# 02_-_Connectors.net
KiCad netlist of a schematic drawn in Altium Designer
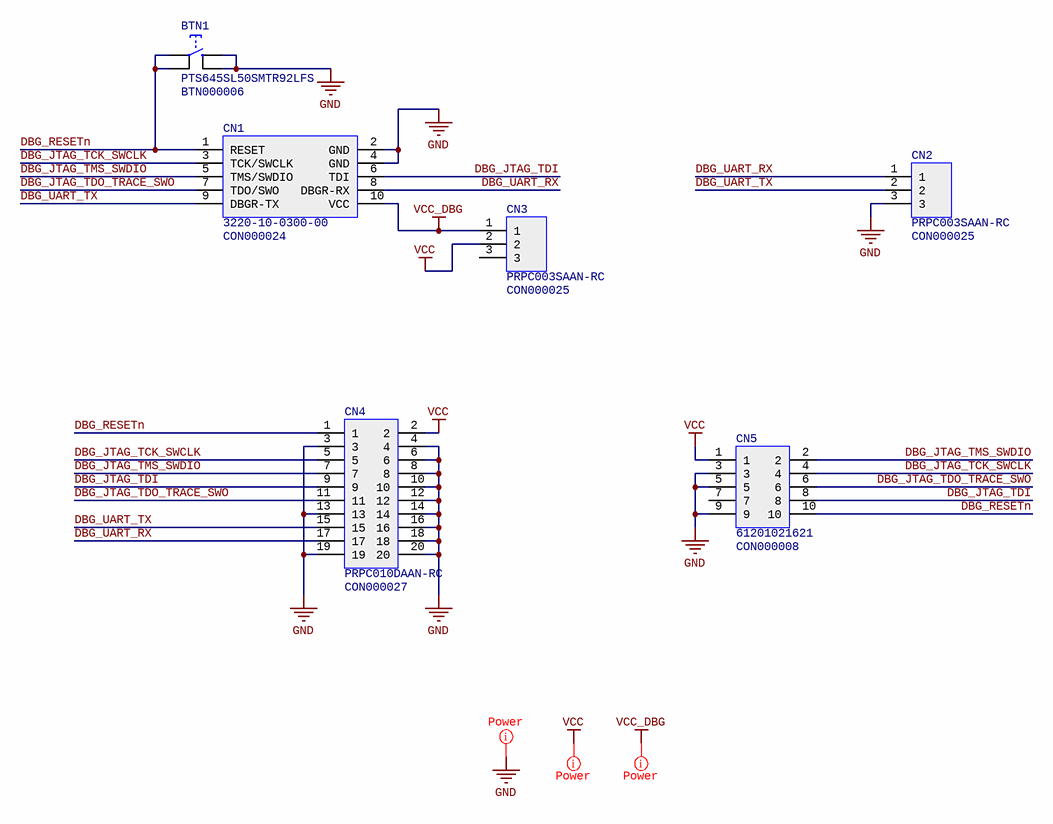
[diagram p0: [02] - Connectors.SchDoc]

(export (version "E")
  (design (tool "Eeschema 10.0.6"))
  (components
    (comp (ref "BTN1")
      (value "PTS645SL50SMTR92LFS")
      (footprint "BTN-SMD-PTS645-CK")
      (description "BTN TACT SPST-NO 12V 50mA SMD BLACK")
      (fields (field (name "MANUFACTURER") "ITT C&K") (field (name "INTERNAL PART NUMBER") "BTN000006"))
      (libsource (lib "Altium_Lib_Standard") (part "PTS645SL50SMTR92LFS"))
    )
    (comp (ref "CN1")
      (value "3220-10-0300-00")
      (footprint "CON-SMD-PINHEADER-SHIELDED-1.27MM-10POS-2X5-3220-10-0300-00-CNC-TECH")
      (description "CON PINHDR SMD 1.27MM SHIELDED KEYED CNC TECH 10POS")
      (fields (field (name "INTERNAL PART NUMBER") "CON000024"))
      (libsource (lib "Altium_Lib_Standard") (part "3220-10-0300-00"))
    )
    (comp (ref "CN2")
      (value "PRPC003SAAN-RC")
      (footprint "CON-THT-PINHEADER-2.54MM-3POS-1X3")
      (description "CON PINHDR 2.54MM 1x03")
      (fields (field (name "MANUFACTURER") "Sullins") (field (name "INTERNAL PART NUMBER") "CON000025"))
      (libsource (lib "Altium_Lib_Standard") (part "PRPC003SAAN-RC"))
    )
    (comp (ref "CN3")
      (value "PRPC003SAAN-RC")
      (footprint "CON-THT-PINHEADER-2.54MM-3POS-1X3")
      (description "CON PINHDR 2.54MM 1x03")
      (fields (field (name "MANUFACTURER") "Sullins") (field (name "INTERNAL PART NUMBER") "CON000025"))
      (libsource (lib "Altium_Lib_Standard") (part "PRPC003SAAN-RC"))
    )
    (comp (ref "CN4")
      (value "PRPC010DAAN-RC")
      (footprint "CON-THT-PINHEADER-2.54MM-20POS-2X10")
      (description "CON PINHDR 2.54MM 2x10")
      (fields (field (name "MANUFACTURER") "Sullins") (field (name "INTERNAL PART NUMBER") "CON000027"))
      (libsource (lib "Altium_Lib_Standard") (part "PRPC010DAAN-RC"))
    )
    (comp (ref "CN5")
      (value "61201021621")
      (footprint "CON-THT-PINHEADER-SHIELDED-2.54MM-10POS-61201021621-WURTH")
      (description "CON PINHDR 2.54MM SHIELDED 2x05 WURTH")
      (fields
        (field (name "MANUFACTURER") "Wurth Electronics")
        (field (name "INTERNAL PART NUMBER") "CON000008")
      )
      (libsource (lib "Altium_Lib_Standard") (part "61201021621"))
    )
  )
  (nets
    (net (code "1") (name "/DBG_JTAG_TCK_SWCLK") (class "Default")
      (node (ref "CN1") (pin "3") (pinfunction "TCK/SWCLK_3") (pintype "passive"))
      (node (ref "CN4") (pin "5") (pinfunction "5_5") (pintype "passive"))
      (node (ref "CN5") (pin "4") (pinfunction "4_4") (pintype "passive"))
    )
    (net (code "2") (name "/DBG_JTAG_TDI") (class "Default")
      (node (ref "CN1") (pin "6") (pinfunction "TDI_6") (pintype "passive"))
      (node (ref "CN4") (pin "9") (pinfunction "9_9") (pintype "passive"))
      (node (ref "CN5") (pin "8") (pinfunction "8_8") (pintype "passive"))
    )
    (net (code "3") (name "/DBG_JTAG_TDO_TRACE_SWO") (class "Default")
      (node (ref "CN1") (pin "7") (pinfunction "TDO/SWO_7") (pintype "passive"))
      (node (ref "CN4") (pin "11") (pinfunction "11_11") (pintype "passive"))
      (node (ref "CN5") (pin "6") (pinfunction "6_6") (pintype "passive"))
    )
    (net (code "4") (name "/DBG_JTAG_TMS_SWDIO") (class "Default")
      (node (ref "CN1") (pin "5") (pinfunction "TMS/SWDIO_5") (pintype "passive"))
      (node (ref "CN4") (pin "7") (pinfunction "7_7") (pintype "passive"))
      (node (ref "CN5") (pin "2") (pinfunction "2_2") (pintype "passive"))
    )
    (net (code "5") (name "/DBG_RESETn") (class "Default")
      (node (ref "BTN1") (pin "1") (pinfunction "1_1") (pintype "passive"))
      (node (ref "BTN1") (pin "2") (pinfunction "2_2") (pintype "passive"))
      (node (ref "CN1") (pin "1") (pinfunction "RESET_1") (pintype "passive"))
      (node (ref "CN4") (pin "1") (pinfunction "1_1") (pintype "passive"))
      (node (ref "CN5") (pin "10") (pinfunction "10_10") (pintype "passive"))
    )
    (net (code "6") (name "/DBG_UART_RX") (class "Default")
      (node (ref "CN1") (pin "8") (pinfunction "DBGR-RX_8") (pintype "passive"))
      (node (ref "CN2") (pin "1") (pinfunction "1_1") (pintype "passive"))
      (node (ref "CN4") (pin "17") (pinfunction "17_17") (pintype "passive"))
    )
    (net (code "7") (name "/DBG_UART_TX") (class "Default")
      (node (ref "CN1") (pin "9") (pinfunction "DBGR-TX_9") (pintype "passive"))
      (node (ref "CN2") (pin "2") (pinfunction "2_2") (pintype "passive"))
      (node (ref "CN4") (pin "15") (pinfunction "15_15") (pintype "passive"))
    )
    (net (code "8") (name "GND") (class "Default")
      (node (ref "BTN1") (pin "3") (pinfunction "3_3") (pintype "passive"))
      (node (ref "BTN1") (pin "4") (pinfunction "4_4") (pintype "passive"))
      (node (ref "CN1") (pin "2") (pinfunction "GND_2") (pintype "passive"))
      (node (ref "CN1") (pin "4") (pinfunction "GND_4") (pintype "passive"))
      (node (ref "CN2") (pin "3") (pinfunction "3_3") (pintype "passive"))
      (node (ref "CN4") (pin "10") (pinfunction "10_10") (pintype "passive"))
      (node (ref "CN4") (pin "12") (pinfunction "12_12") (pintype "passive"))
      (node (ref "CN4") (pin "13") (pinfunction "13_13") (pintype "passive"))
      (node (ref "CN4") (pin "14") (pinfunction "14_14") (pintype "passive"))
      (node (ref "CN4") (pin "16") (pinfunction "16_16") (pintype "passive"))
      (node (ref "CN4") (pin "18") (pinfunction "18_18") (pintype "passive"))
      (node (ref "CN4") (pin "19") (pinfunction "19_19") (pintype "passive"))
      (node (ref "CN4") (pin "20") (pinfunction "20_20") (pintype "passive"))
      (node (ref "CN4") (pin "3") (pinfunction "3_3") (pintype "passive"))
      (node (ref "CN4") (pin "4") (pinfunction "4_4") (pintype "passive"))
      (node (ref "CN4") (pin "6") (pinfunction "6_6") (pintype "passive"))
      (node (ref "CN4") (pin "8") (pinfunction "8_8") (pintype "passive"))
      (node (ref "CN5") (pin "3") (pinfunction "3_3") (pintype "passive"))
      (node (ref "CN5") (pin "5") (pinfunction "5_5") (pintype "passive"))
      (node (ref "CN5") (pin "9") (pinfunction "9_9") (pintype "passive"))
    )
    (net (code "9") (name "VCC") (class "Default")
      (node (ref "CN3") (pin "2") (pinfunction "2_2") (pintype "passive"))
      (node (ref "CN4") (pin "2") (pinfunction "2_2") (pintype "passive"))
      (node (ref "CN5") (pin "1") (pinfunction "1_1") (pintype "passive"))
    )
    (net (code "10") (name "VCC_DBG") (class "Default")
      (node (ref "CN1") (pin "10") (pinfunction "VCC_10") (pintype "passive"))
      (node (ref "CN3") (pin "1") (pinfunction "1_1") (pintype "passive"))
    )
    (net (code "11") (name "unconnected-(CN3-Pad3)") (class "Default")
      (node (ref "CN3") (pin "3") (pinfunction "3_3") (pintype "passive"))
    )
    (net (code "12") (name "unconnected-(CN5-Pad7)") (class "Default")
      (node (ref "CN5") (pin "7") (pinfunction "7_7") (pintype "passive"))
    )
  )
)
